# lyre_v1.net
KiCad netlist of a schematic drawn in EAGLE
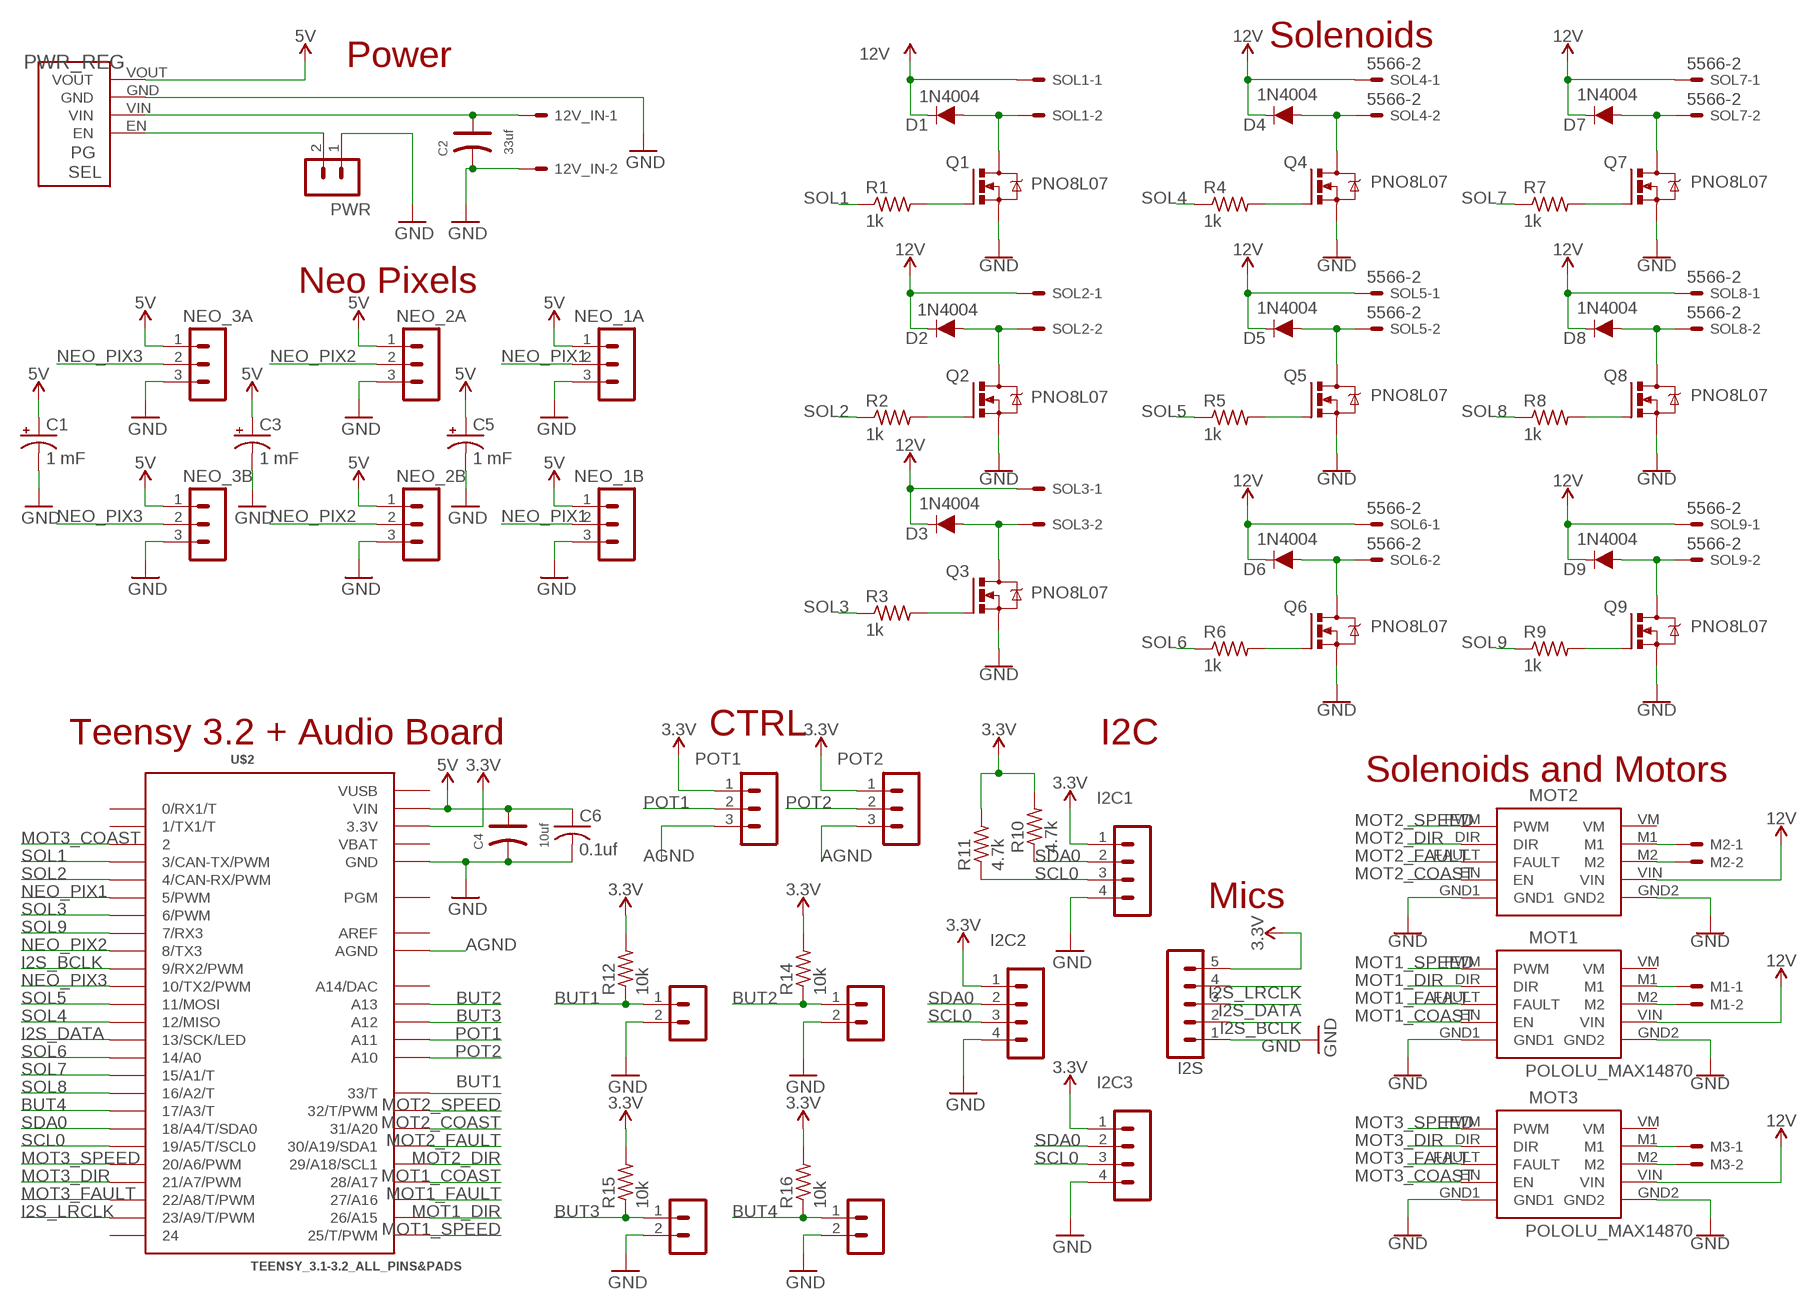
[diagram p0: schematic, sheet 1]

(export (version "E")
  (design (tool "Eeschema 10.0.6"))
  (components
    (comp (ref "12V_IN")
      (value "5566-2")
      (footprint "eagle-import:5566-2")
      (fields (field (name "MF") "MOLEX"))
      (libsource (lib "eagle-import") (part "5566-2"))
    )
    (comp (ref "BUT1")
      (value "B2B-PH-K")
      (footprint "eagle-import:B2B-PH-K")
      (libsource (lib "eagle-import") (part "B2B-PH-K"))
    )
    (comp (ref "BUT2")
      (value "B2B-PH-K")
      (footprint "eagle-import:B2B-PH-K")
      (libsource (lib "eagle-import") (part "B2B-PH-K"))
    )
    (comp (ref "BUT3")
      (value "B2B-PH-K")
      (footprint "eagle-import:B2B-PH-K")
      (libsource (lib "eagle-import") (part "B2B-PH-K"))
    )
    (comp (ref "BUT4")
      (value "B2B-PH-K")
      (footprint "eagle-import:B2B-PH-K")
      (libsource (lib "eagle-import") (part "B2B-PH-K"))
    )
    (comp (ref "C1")
      (value "1 mF")
      (footprint "eagle-import:UD-10X10_NICHICON")
      (libsource (lib "eagle-import") (part "CPOL-USUD-10X10"))
    )
    (comp (ref "C2")
      (value "33uf")
      (footprint "eagle-import:PC-D5.3MM")
      (fields (field (name "MPN") "KS 100uF/16V"))
      (libsource (lib "eagle-import") (part "DIP-ALUMINUM-47UF-16V(D5-H7MM)"))
    )
    (comp (ref "C3")
      (value "1 mF")
      (footprint "eagle-import:UD-10X10_NICHICON")
      (libsource (lib "eagle-import") (part "CPOL-USUD-10X10"))
    )
    (comp (ref "C4")
      (value "10uf")
      (footprint "eagle-import:PC-D5.3MM")
      (fields (field (name "MPN") "KS 100uF/16V"))
      (libsource (lib "eagle-import") (part "DIP-ALUMINUM-47UF-16V(D5-H7MM)"))
    )
    (comp (ref "C5")
      (value "1 mF")
      (footprint "eagle-import:UD-10X10_NICHICON")
      (libsource (lib "eagle-import") (part "CPOL-USUD-10X10"))
    )
    (comp (ref "C6")
      (value "0.1uf")
      (footprint "eagle-import:C2012")
      (libsource (lib "eagle-import") (part "C-USC2012"))
    )
    (comp (ref "D1")
      (value "1N4004")
      (footprint "eagle-import:DIOAD1138W86L465D235B")
      (libsource (lib "eagle-import") (part "1N4004"))
    )
    (comp (ref "D2")
      (value "1N4004")
      (footprint "eagle-import:DIOAD1138W86L465D235B")
      (libsource (lib "eagle-import") (part "1N4004"))
    )
    (comp (ref "D3")
      (value "1N4004")
      (footprint "eagle-import:DIOAD1138W86L465D235B")
      (libsource (lib "eagle-import") (part "1N4004"))
    )
    (comp (ref "D4")
      (value "1N4004")
      (footprint "eagle-import:DIOAD1138W86L465D235B")
      (libsource (lib "eagle-import") (part "1N4004"))
    )
    (comp (ref "D5")
      (value "1N4004")
      (footprint "eagle-import:DIOAD1138W86L465D235B")
      (libsource (lib "eagle-import") (part "1N4004"))
    )
    (comp (ref "D6")
      (value "1N4004")
      (footprint "eagle-import:DIOAD1138W86L465D235B")
      (libsource (lib "eagle-import") (part "1N4004"))
    )
    (comp (ref "D7")
      (value "1N4004")
      (footprint "eagle-import:DIOAD1138W86L465D235B")
      (libsource (lib "eagle-import") (part "1N4004"))
    )
    (comp (ref "D8")
      (value "1N4004")
      (footprint "eagle-import:DIOAD1138W86L465D235B")
      (libsource (lib "eagle-import") (part "1N4004"))
    )
    (comp (ref "D9")
      (value "1N4004")
      (footprint "eagle-import:DIOAD1138W86L465D235B")
      (libsource (lib "eagle-import") (part "1N4004"))
    )
    (comp (ref "I2C1")
      (value "B4B-PH-K")
      (footprint "eagle-import:B4B-PH-K")
      (libsource (lib "eagle-import") (part "B4B-PH-K"))
    )
    (comp (ref "I2C2")
      (value "B4B-PH-K")
      (footprint "eagle-import:B4B-PH-K")
      (libsource (lib "eagle-import") (part "B4B-PH-K"))
    )
    (comp (ref "I2C3")
      (value "B4B-PH-K")
      (footprint "eagle-import:B4B-PH-K")
      (libsource (lib "eagle-import") (part "B4B-PH-K"))
    )
    (comp (ref "I2S")
      (value "B5B-PH-K")
      (footprint "eagle-import:B5B-PH-K")
      (libsource (lib "eagle-import") (part "B5B-PH-K"))
    )
    (comp (ref "M1")
      (value "5566-2")
      (footprint "eagle-import:5566-2")
      (fields (field (name "MF") "MOLEX"))
      (libsource (lib "eagle-import") (part "5566-2"))
    )
    (comp (ref "M2")
      (value "5566-2")
      (footprint "eagle-import:5566-2")
      (fields (field (name "MF") "MOLEX"))
      (libsource (lib "eagle-import") (part "5566-2"))
    )
    (comp (ref "M3")
      (value "5566-2")
      (footprint "eagle-import:5566-2")
      (fields (field (name "MF") "MOLEX"))
      (libsource (lib "eagle-import") (part "5566-2"))
    )
    (comp (ref "MOT1")
      (value "POLOLU_MAX14870")
      (footprint "eagle-import:POLOLU_MAX14870")
      (libsource (lib "eagle-import") (part "POLOLU_MAX14870"))
    )
    (comp (ref "MOT2")
      (value "POLOLU_MAX14870")
      (footprint "eagle-import:POLOLU_MAX14870")
      (libsource (lib "eagle-import") (part "POLOLU_MAX14870"))
    )
    (comp (ref "MOT3")
      (value "POLOLU_MAX14870")
      (footprint "eagle-import:POLOLU_MAX14870")
      (libsource (lib "eagle-import") (part "POLOLU_MAX14870"))
    )
    (comp (ref "NEO_1A")
      (value "B3B-PH-K")
      (footprint "eagle-import:B3B-PH-K")
      (libsource (lib "eagle-import") (part "B3B-PH-K"))
    )
    (comp (ref "NEO_1B")
      (value "B3B-PH-K")
      (footprint "eagle-import:B3B-PH-K")
      (libsource (lib "eagle-import") (part "B3B-PH-K"))
    )
    (comp (ref "NEO_2A")
      (value "B3B-PH-K")
      (footprint "eagle-import:B3B-PH-K")
      (libsource (lib "eagle-import") (part "B3B-PH-K"))
    )
    (comp (ref "NEO_2B")
      (value "B3B-PH-K")
      (footprint "eagle-import:B3B-PH-K")
      (libsource (lib "eagle-import") (part "B3B-PH-K"))
    )
    (comp (ref "NEO_3A")
      (value "B3B-PH-K")
      (footprint "eagle-import:B3B-PH-K")
      (libsource (lib "eagle-import") (part "B3B-PH-K"))
    )
    (comp (ref "NEO_3B")
      (value "B3B-PH-K")
      (footprint "eagle-import:B3B-PH-K")
      (libsource (lib "eagle-import") (part "B3B-PH-K"))
    )
    (comp (ref "POT1")
      (value "B3B-PH-K")
      (footprint "eagle-import:B3B-PH-K")
      (libsource (lib "eagle-import") (part "B3B-PH-K"))
    )
    (comp (ref "POT2")
      (value "B3B-PH-K")
      (footprint "eagle-import:B3B-PH-K")
      (libsource (lib "eagle-import") (part "B3B-PH-K"))
    )
    (comp (ref "PWR")
      (value "B2B-PH-K")
      (footprint "eagle-import:B2B-PH-K")
      (libsource (lib "eagle-import") (part "B2B-PH-K"))
    )
    (comp (ref "PWR_REG")
      (value "S9V11F5S6CMA_MISSINIG_PINS")
      (footprint "eagle-import:S9V11F3S5CMA_MISSING_PINS")
      (libsource (lib "eagle-import") (part "S9V11F5S6CMA_MISSINIG_PINS"))
    )
    (comp (ref "Q1")
      (value "PNO8L07")
      (footprint "eagle-import:TO220BV")
      (libsource (lib "eagle-import") (part "IRF540"))
    )
    (comp (ref "Q2")
      (value "PNO8L07")
      (footprint "eagle-import:TO220BV")
      (libsource (lib "eagle-import") (part "IRF540"))
    )
    (comp (ref "Q3")
      (value "PNO8L07")
      (footprint "eagle-import:TO220BV")
      (libsource (lib "eagle-import") (part "IRF540"))
    )
    (comp (ref "Q4")
      (value "PNO8L07")
      (footprint "eagle-import:TO220BV")
      (libsource (lib "eagle-import") (part "IRF540"))
    )
    (comp (ref "Q5")
      (value "PNO8L07")
      (footprint "eagle-import:TO220BV")
      (libsource (lib "eagle-import") (part "IRF540"))
    )
    (comp (ref "Q6")
      (value "PNO8L07")
      (footprint "eagle-import:TO220BV")
      (libsource (lib "eagle-import") (part "IRF540"))
    )
    (comp (ref "Q7")
      (value "PNO8L07")
      (footprint "eagle-import:TO220BV")
      (libsource (lib "eagle-import") (part "IRF540"))
    )
    (comp (ref "Q8")
      (value "PNO8L07")
      (footprint "eagle-import:TO220BV")
      (libsource (lib "eagle-import") (part "IRF540"))
    )
    (comp (ref "Q9")
      (value "PNO8L07")
      (footprint "eagle-import:TO220BV")
      (libsource (lib "eagle-import") (part "IRF540"))
    )
    (comp (ref "R1")
      (value "1k")
      (footprint "eagle-import:R0805")
      (libsource (lib "eagle-import") (part "R-US_R0805"))
    )
    (comp (ref "R2")
      (value "1k")
      (footprint "eagle-import:R0805")
      (libsource (lib "eagle-import") (part "R-US_R0805"))
    )
    (comp (ref "R3")
      (value "1k")
      (footprint "eagle-import:R0805")
      (libsource (lib "eagle-import") (part "R-US_R0805"))
    )
    (comp (ref "R4")
      (value "1k")
      (footprint "eagle-import:R0805")
      (libsource (lib "eagle-import") (part "R-US_R0805"))
    )
    (comp (ref "R5")
      (value "1k")
      (footprint "eagle-import:R0805")
      (libsource (lib "eagle-import") (part "R-US_R0805"))
    )
    (comp (ref "R6")
      (value "1k")
      (footprint "eagle-import:R0805")
      (libsource (lib "eagle-import") (part "R-US_R0805"))
    )
    (comp (ref "R7")
      (value "1k")
      (footprint "eagle-import:R0805")
      (libsource (lib "eagle-import") (part "R-US_R0805"))
    )
    (comp (ref "R8")
      (value "1k")
      (footprint "eagle-import:R0805")
      (libsource (lib "eagle-import") (part "R-US_R0805"))
    )
    (comp (ref "R9")
      (value "1k")
      (footprint "eagle-import:R0805")
      (libsource (lib "eagle-import") (part "R-US_R0805"))
    )
    (comp (ref "R10")
      (value "4.7k")
      (footprint "eagle-import:R0805")
      (libsource (lib "eagle-import") (part "R-US_R0805"))
    )
    (comp (ref "R11")
      (value "4.7k")
      (footprint "eagle-import:R0805")
      (libsource (lib "eagle-import") (part "R-US_R0805"))
    )
    (comp (ref "R12")
      (value "10k")
      (footprint "eagle-import:R0805")
      (libsource (lib "eagle-import") (part "R-US_R0805"))
    )
    (comp (ref "R14")
      (value "10k")
      (footprint "eagle-import:R0805")
      (libsource (lib "eagle-import") (part "R-US_R0805"))
    )
    (comp (ref "R15")
      (value "10k")
      (footprint "eagle-import:R0805")
      (libsource (lib "eagle-import") (part "R-US_R0805"))
    )
    (comp (ref "R16")
      (value "10k")
      (footprint "eagle-import:R0805")
      (libsource (lib "eagle-import") (part "R-US_R0805"))
    )
    (comp (ref "SOL1")
      (value "5566-2")
      (footprint "eagle-import:5566-2")
      (fields (field (name "MF") "MOLEX"))
      (libsource (lib "eagle-import") (part "5566-2"))
    )
    (comp (ref "SOL2")
      (value "5566-2")
      (footprint "eagle-import:5566-2")
      (fields (field (name "MF") "MOLEX"))
      (libsource (lib "eagle-import") (part "5566-2"))
    )
    (comp (ref "SOL3")
      (value "5566-2")
      (footprint "eagle-import:5566-2")
      (fields (field (name "MF") "MOLEX"))
      (libsource (lib "eagle-import") (part "5566-2"))
    )
    (comp (ref "SOL4")
      (value "5566-2")
      (footprint "eagle-import:5566-2")
      (fields (field (name "MF") "MOLEX"))
      (libsource (lib "eagle-import") (part "5566-2"))
    )
    (comp (ref "SOL5")
      (value "5566-2")
      (footprint "eagle-import:5566-2")
      (fields (field (name "MF") "MOLEX"))
      (libsource (lib "eagle-import") (part "5566-2"))
    )
    (comp (ref "SOL6")
      (value "5566-2")
      (footprint "eagle-import:5566-2")
      (fields (field (name "MF") "MOLEX"))
      (libsource (lib "eagle-import") (part "5566-2"))
    )
    (comp (ref "SOL7")
      (value "5566-2")
      (footprint "eagle-import:5566-2")
      (fields (field (name "MF") "MOLEX"))
      (libsource (lib "eagle-import") (part "5566-2"))
    )
    (comp (ref "SOL8")
      (value "5566-2")
      (footprint "eagle-import:5566-2")
      (fields (field (name "MF") "MOLEX"))
      (libsource (lib "eagle-import") (part "5566-2"))
    )
    (comp (ref "SOL9")
      (value "5566-2")
      (footprint "eagle-import:5566-2")
      (fields (field (name "MF") "MOLEX"))
      (libsource (lib "eagle-import") (part "5566-2"))
    )
    (comp (ref "U$2")
      (value "TEENSY_3.1-3.2_ALL_PINS&PADS")
      (footprint "eagle-import:TEENSY_3.0-3.2_ALL_PINS_&_PADS")
      (libsource (lib "eagle-import") (part "TEENSY_3.1-3.2_ALL_PINS&PADS"))
    )
  )
  (nets
    (net (code "1") (name "/AGND") (class "Default")
      (node (ref "POT1") (pin "3") (pinfunction "3_3") (pintype "passive"))
      (node (ref "POT2") (pin "3") (pinfunction "3_3") (pintype "passive"))
      (node (ref "U$2") (pin "AGND") (pinfunction "AGND_AGND") (pintype "power_in"))
    )
    (net (code "2") (name "/AREF") (class "Default")
      (node (ref "U$2") (pin "AREF") (pinfunction "AREF_AREF") (pintype "power_in"))
    )
    (net (code "3") (name "/BUT1") (class "Default")
      (node (ref "BUT1") (pin "1") (pinfunction "1_1") (pintype "passive"))
      (node (ref "R12") (pin "1") (pinfunction "1_1") (pintype "passive"))
      (node (ref "U$2") (pin "33") (pinfunction "33/T_33") (pintype "bidirectional"))
    )
    (net (code "4") (name "/BUT2") (class "Default")
      (node (ref "BUT2") (pin "1") (pinfunction "1_1") (pintype "passive"))
      (node (ref "R14") (pin "1") (pinfunction "1_1") (pintype "passive"))
      (node (ref "U$2") (pin "A13") (pinfunction "A13_A13") (pintype "bidirectional"))
    )
    (net (code "5") (name "/BUT3") (class "Default")
      (node (ref "BUT3") (pin "1") (pinfunction "1_1") (pintype "passive"))
      (node (ref "R15") (pin "1") (pinfunction "1_1") (pintype "passive"))
      (node (ref "U$2") (pin "A12") (pinfunction "A12_A12") (pintype "bidirectional"))
    )
    (net (code "6") (name "/BUT4") (class "Default")
      (node (ref "BUT4") (pin "1") (pinfunction "1_1") (pintype "passive"))
      (node (ref "R16") (pin "1") (pinfunction "1_1") (pintype "passive"))
      (node (ref "U$2") (pin "17/A3") (pinfunction "17/A3/T_17/A3") (pintype "bidirectional"))
    )
    (net (code "7") (name "/I2S_BCLK") (class "Default")
      (node (ref "I2S") (pin "2") (pinfunction "2_2") (pintype "passive"))
      (node (ref "U$2") (pin "9") (pinfunction "9/RX2/PWM_9") (pintype "bidirectional"))
    )
    (net (code "8") (name "/I2S_DATA") (class "Default")
      (node (ref "I2S") (pin "3") (pinfunction "3_3") (pintype "passive"))
      (node (ref "U$2") (pin "13") (pinfunction "13/SCK/LED_13") (pintype "bidirectional"))
    )
    (net (code "9") (name "/I2S_LRCLK") (class "Default")
      (node (ref "I2S") (pin "4") (pinfunction "4_4") (pintype "passive"))
      (node (ref "U$2") (pin "23/A9") (pinfunction "23/A9/T/PWM_23/A9") (pintype "bidirectional"))
    )
    (net (code "10") (name "/MOT1_COAST") (class "Default")
      (node (ref "MOT1") (pin "EN") (pinfunction "EN_EN") (pintype "bidirectional"))
      (node (ref "U$2") (pin "28") (pinfunction "28/A17_28") (pintype "bidirectional"))
    )
    (net (code "11") (name "/MOT1_DIR") (class "Default")
      (node (ref "MOT1") (pin "DIR") (pinfunction "DIR_DIR") (pintype "bidirectional"))
      (node (ref "U$2") (pin "26") (pinfunction "26/A15_26") (pintype "bidirectional"))
    )
    (net (code "12") (name "/MOT1_FAULT") (class "Default")
      (node (ref "MOT1") (pin "FAULT") (pinfunction "FAULT_FAULT") (pintype "bidirectional"))
      (node (ref "U$2") (pin "27") (pinfunction "27/A16_27") (pintype "bidirectional"))
    )
    (net (code "13") (name "/MOT1_SPEED") (class "Default")
      (node (ref "MOT1") (pin "PWM") (pinfunction "PWM_PWM") (pintype "bidirectional"))
      (node (ref "U$2") (pin "25") (pinfunction "25/T/PWM_25") (pintype "bidirectional"))
    )
    (net (code "14") (name "/MOT2_COAST") (class "Default")
      (node (ref "MOT2") (pin "EN") (pinfunction "EN_EN") (pintype "bidirectional"))
      (node (ref "U$2") (pin "31") (pinfunction "31/A20_31") (pintype "bidirectional"))
    )
    (net (code "15") (name "/MOT2_DIR") (class "Default")
      (node (ref "MOT2") (pin "DIR") (pinfunction "DIR_DIR") (pintype "bidirectional"))
      (node (ref "U$2") (pin "29") (pinfunction "29/A18/SCL1_29") (pintype "bidirectional"))
    )
    (net (code "16") (name "/MOT2_FAULT") (class "Default")
      (node (ref "MOT2") (pin "FAULT") (pinfunction "FAULT_FAULT") (pintype "bidirectional"))
      (node (ref "U$2") (pin "30") (pinfunction "30/A19/SDA1_30") (pintype "bidirectional"))
    )
    (net (code "17") (name "/MOT2_SPEED") (class "Default")
      (node (ref "MOT2") (pin "PWM") (pinfunction "PWM_PWM") (pintype "bidirectional"))
      (node (ref "U$2") (pin "32") (pinfunction "32/T/PWM_32") (pintype "bidirectional"))
    )
    (net (code "18") (name "/MOT3_COAST") (class "Default")
      (node (ref "MOT3") (pin "EN") (pinfunction "EN_EN") (pintype "bidirectional"))
      (node (ref "U$2") (pin "2") (pinfunction "2_2") (pintype "bidirectional"))
    )
    (net (code "19") (name "/MOT3_DIR") (class "Default")
      (node (ref "MOT3") (pin "DIR") (pinfunction "DIR_DIR") (pintype "bidirectional"))
      (node (ref "U$2") (pin "21/A7") (pinfunction "21/A7/PWM_21/A7") (pintype "bidirectional"))
    )
    (net (code "20") (name "/MOT3_FAULT") (class "Default")
      (node (ref "MOT3") (pin "FAULT") (pinfunction "FAULT_FAULT") (pintype "bidirectional"))
      (node (ref "U$2") (pin "22/A8") (pinfunction "22/A8/T/PWM_22/A8") (pintype "bidirectional"))
    )
    (net (code "21") (name "/MOT3_SPEED") (class "Default")
      (node (ref "MOT3") (pin "PWM") (pinfunction "PWM_PWM") (pintype "bidirectional"))
      (node (ref "U$2") (pin "20/A6") (pinfunction "20/A6/PWM_20/A6") (pintype "bidirectional"))
    )
    (net (code "22") (name "/NEO_PIX1") (class "Default")
      (node (ref "NEO_1A") (pin "2") (pinfunction "2_2") (pintype "passive"))
      (node (ref "NEO_1B") (pin "2") (pinfunction "2_2") (pintype "passive"))
      (node (ref "U$2") (pin "5") (pinfunction "5/PWM_5") (pintype "bidirectional"))
    )
    (net (code "23") (name "/NEO_PIX2") (class "Default")
      (node (ref "NEO_2A") (pin "2") (pinfunction "2_2") (pintype "passive"))
      (node (ref "NEO_2B") (pin "2") (pinfunction "2_2") (pintype "passive"))
      (node (ref "U$2") (pin "8") (pinfunction "8/TX3_8") (pintype "bidirectional"))
    )
    (net (code "24") (name "/NEO_PIX3") (class "Default")
      (node (ref "NEO_3A") (pin "2") (pinfunction "2_2") (pintype "passive"))
      (node (ref "NEO_3B") (pin "2") (pinfunction "2_2") (pintype "passive"))
      (node (ref "U$2") (pin "10") (pinfunction "10/TX2/PWM_10") (pintype "bidirectional"))
    )
    (net (code "25") (name "/POT1") (class "Default")
      (node (ref "POT1") (pin "2") (pinfunction "2_2") (pintype "passive"))
      (node (ref "U$2") (pin "A11") (pinfunction "A11_A11") (pintype "bidirectional"))
    )
    (net (code "26") (name "/POT2") (class "Default")
      (node (ref "POT2") (pin "2") (pinfunction "2_2") (pintype "passive"))
      (node (ref "U$2") (pin "A10") (pinfunction "A10_A10") (pintype "bidirectional"))
    )
    (net (code "27") (name "/SCL0") (class "Default")
      (node (ref "I2C1") (pin "3") (pinfunction "3_3") (pintype "passive"))
      (node (ref "I2C2") (pin "3") (pinfunction "3_3") (pintype "passive"))
      (node (ref "I2C3") (pin "3") (pinfunction "3_3") (pintype "passive"))
      (node (ref "R11") (pin "1") (pinfunction "1_1") (pintype "passive"))
      (node (ref "U$2") (pin "19/A5") (pinfunction "19/A5/T/SCL0_19/A5") (pintype "bidirectional"))
    )
    (net (code "28") (name "/SDA0") (class "Default")
      (node (ref "I2C1") (pin "2") (pinfunction "2_2") (pintype "passive"))
      (node (ref "I2C2") (pin "2") (pinfunction "2_2") (pintype "passive"))
      (node (ref "I2C3") (pin "2") (pinfunction "2_2") (pintype "passive"))
      (node (ref "R10") (pin "1") (pinfunction "1_1") (pintype "passive"))
      (node (ref "U$2") (pin "18/A4") (pinfunction "18/A4/T/SDA0_18/A4") (pintype "bidirectional"))
    )
    (net (code "29") (name "/SOL1") (class "Default")
      (node (ref "R1") (pin "1") (pinfunction "1_1") (pintype "passive"))
      (node (ref "U$2") (pin "3") (pinfunction "3/CAN-TX/PWM_3") (pintype "bidirectional"))
    )
    (net (code "30") (name "/SOL2") (class "Default")
      (node (ref "R2") (pin "1") (pinfunction "1_1") (pintype "passive"))
      (node (ref "U$2") (pin "4") (pinfunction "4/CAN-RX/PWM_4") (pintype "bidirectional"))
    )
    (net (code "31") (name "/SOL3") (class "Default")
      (node (ref "R3") (pin "1") (pinfunction "1_1") (pintype "passive"))
      (node (ref "U$2") (pin "6") (pinfunction "6/PWM_6") (pintype "bidirectional"))
    )
    (net (code "32") (name "/SOL4") (class "Default")
      (node (ref "R4") (pin "1") (pinfunction "1_1") (pintype "passive"))
      (node (ref "U$2") (pin "12") (pinfunction "12/MISO_12") (pintype "bidirectional"))
    )
    (net (code "33") (name "/SOL5") (class "Default")
      (node (ref "R5") (pin "1") (pinfunction "1_1") (pintype "passive"))
      (node (ref "U$2") (pin "11") (pinfunction "11/MOSI_11") (pintype "bidirectional"))
    )
    (net (code "34") (name "/SOL6") (class "Default")
      (node (ref "R6") (pin "1") (pinfunction "1_1") (pintype "passive"))
      (node (ref "U$2") (pin "14/A0") (pinfunction "14/A0_14/A0") (pintype "bidirectional"))
    )
    (net (code "35") (name "/SOL7") (class "Default")
      (node (ref "R7") (pin "1") (pinfunction "1_1") (pintype "passive"))
      (node (ref "U$2") (pin "15/A1") (pinfunction "15/A1/T_15/A1") (pintype "bidirectional"))
    )
    (net (code "36") (name "/SOL8") (class "Default")
      (node (ref "R8") (pin "1") (pinfunction "1_1") (pintype "passive"))
      (node (ref "U$2") (pin "16/A2") (pinfunction "16/A2/T_16/A2") (pintype "bidirectional"))
    )
    (net (code "37") (name "/SOL9") (class "Default")
      (node (ref "R9") (pin "1") (pinfunction "1_1") (pintype "passive"))
      (node (ref "U$2") (pin "7") (pinfunction "7/RX3_7") (pintype "bidirectional"))
    )
    (net (code "38") (name "/VBAT") (class "Default")
      (node (ref "U$2") (pin "VBAT") (pinfunction "VBAT_VBAT") (pintype "power_in"))
    )
    (net (code "39") (name "/VUSB") (class "Default")
      (node (ref "U$2") (pin "VUSB") (pinfunction "VUSB_VUSB") (pintype "power_in"))
    )
    (net (code "40") (name "3.3V") (class "Default")
      (node (ref "I2C1") (pin "1") (pinfunction "1_1") (pintype "passive"))
      (node (ref "I2C2") (pin "1") (pinfunction "1_1") (pintype "passive"))
      (node (ref "I2C3") (pin "1") (pinfunction "1_1") (pintype "passive"))
      (node (ref "I2S") (pin "5") (pinfunction "5_5") (pintype "passive"))
      (node (ref "POT1") (pin "1") (pinfunction "1_1") (pintype "passive"))
      (node (ref "POT2") (pin "1") (pinfunction "1_1") (pintype "passive"))
      (node (ref "R10") (pin "2") (pinfunction "2_2") (pintype "passive"))
      (node (ref "R11") (pin "2") (pinfunction "2_2") (pintype "passive"))
      (node (ref "R12") (pin "2") (pinfunction "2_2") (pintype "passive"))
      (node (ref "R14") (pin "2") (pinfunction "2_2") (pintype "passive"))
      (node (ref "R15") (pin "2") (pinfunction "2_2") (pintype "passive"))
      (node (ref "R16") (pin "2") (pinfunction "2_2") (pintype "passive"))
      (node (ref "U$2") (pin "3.3V") (pinfunction "3.3V_3.3V") (pintype "power_in"))
      (node (ref "U$2") (pin "3.3V1") (pinfunction "3.3V_3.3V1") (pintype "power_in"))
      (node (ref "U$2") (pin "3.3V2") (pinfunction "3.3V_3.3V2") (pintype "power_in"))
    )
    (net (code "41") (name "5V") (class "Default")
      (node (ref "C1") (pin "+") (pinfunction "+_+") (pintype "passive"))
      (node (ref "C3") (pin "+") (pinfunction "+_+") (pintype "passive"))
      (node (ref "C4") (pin "+") (pinfunction "+_+") (pintype "passive"))
      (node (ref "C5") (pin "+") (pinfunction "+_+") (pintype "passive"))
      (node (ref "C6") (pin "1") (pinfunction "1_1") (pintype "passive"))
      (node (ref "NEO_1A") (pin "1") (pinfunction "1_1") (pintype "passive"))
      (node (ref "NEO_1B") (pin "1") (pinfunction "1_1") (pintype "passive"))
      (node (ref "NEO_2A") (pin "1") (pinfunction "1_1") (pintype "passive"))
      (node (ref "NEO_2B") (pin "1") (pinfunction "1_1") (pintype "passive"))
      (node (ref "NEO_3A") (pin "1") (pinfunction "1_1") (pintype "passive"))
      (node (ref "NEO_3B") (pin "1") (pinfunction "1_1") (pintype "passive"))
      (node (ref "PWR_REG") (pin "VOUT") (pinfunction "VOUT_VOUT") (pintype "bidirectional"))
      (node (ref "U$2") (pin "VIN") (pinfunction "VIN_VIN") (pintype "power_in"))
    )
    (net (code "42") (name "12V") (class "Default")
      (node (ref "12V_IN") (pin "1") (pinfunction "S_1") (pintype "passive"))
      (node (ref "C2") (pin "+") (pinfunction "+_+") (pintype "passive"))
      (node (ref "D1") (pin "2") (pinfunction "C_2") (pintype "passive"))
      (node (ref "D2") (pin "2") (pinfunction "C_2") (pintype "passive"))
      (node (ref "D3") (pin "2") (pinfunction "C_2") (pintype "passive"))
      (node (ref "D4") (pin "2") (pinfunction "C_2") (pintype "passive"))
      (node (ref "D5") (pin "2") (pinfunction "C_2") (pintype "passive"))
      (node (ref "D6") (pin "2") (pinfunction "C_2") (pintype "passive"))
      (node (ref "D7") (pin "2") (pinfunction "C_2") (pintype "passive"))
      (node (ref "D8") (pin "2") (pinfunction "C_2") (pintype "passive"))
      (node (ref "D9") (pin "2") (pinfunction "C_2") (pintype "passive"))
      (node (ref "MOT1") (pin "VIN") (pinfunction "VIN_VIN") (pintype "bidirectional"))
      (node (ref "MOT2") (pin "VIN") (pinfunction "VIN_VIN") (pintype "bidirectional"))
      (node (ref "MOT3") (pin "VIN") (pinfunction "VIN_VIN") (pintype "bidirectional"))
      (node (ref "PWR_REG") (pin "VIN") (pinfunction "VIN_VIN") (pintype "bidirectional"))
      (node (ref "SOL1") (pin "1") (pinfunction "S_1") (pintype "passive"))
      (node (ref "SOL2") (pin "1") (pinfunction "S_1") (pintype "passive"))
      (node (ref "SOL3") (pin "1") (pinfunction "S_1") (pintype "passive"))
      (node (ref "SOL4") (pin "1") (pinfunction "S_1") (pintype "passive"))
      (node (ref "SOL5") (pin "1") (pinfunction "S_1") (pintype "passive"))
      (node (ref "SOL6") (pin "1") (pinfunction "S_1") (pintype "passive"))
      (node (ref "SOL7") (pin "1") (pinfunction "S_1") (pintype "passive"))
      (node (ref "SOL8") (pin "1") (pinfunction "S_1") (pintype "passive"))
      (node (ref "SOL9") (pin "1") (pinfunction "S_1") (pintype "passive"))
    )
    (net (code "43") (name "GND") (class "Default")
      (node (ref "12V_IN") (pin "2") (pinfunction "S_2") (pintype "passive"))
      (node (ref "BUT1") (pin "2") (pinfunction "2_2") (pintype "passive"))
      (node (ref "BUT2") (pin "2") (pinfunction "2_2") (pintype "passive"))
      (node (ref "BUT3") (pin "2") (pinfunction "2_2") (pintype "passive"))
      (node (ref "BUT4") (pin "2") (pinfunction "2_2") (pintype "passive"))
      (node (ref "C1") (pin "-") (pinfunction "-_-") (pintype "passive"))
      (node (ref "C2") (pin "-") (pinfunction "-_-") (pintype "passive"))
      (node (ref "C3") (pin "-") (pinfunction "-_-") (pintype "passive"))
      (node (ref "C4") (pin "-") (pinfunction "-_-") (pintype "passive"))
      (node (ref "C5") (pin "-") (pinfunction "-_-") (pintype "passive"))
      (node (ref "C6") (pin "2") (pinfunction "2_2") (pintype "passive"))
      (node (ref "I2C1") (pin "4") (pinfunction "4_4") (pintype "passive"))
      (node (ref "I2C2") (pin "4") (pinfunction "4_4") (pintype "passive"))
      (node (ref "I2C3") (pin "4") (pinfunction "4_4") (pintype "passive"))
      (node (ref "I2S") (pin "1") (pinfunction "1_1") (pintype "passive"))
      (node (ref "MOT1") (pin "GND1") (pinfunction "GND1_GND1") (pintype "bidirectional"))
      (node (ref "MOT1") (pin "GND2") (pinfunction "GND2_GND2") (pintype "bidirectional"))
      (node (ref "MOT2") (pin "GND1") (pinfunction "GND1_GND1") (pintype "bidirectional"))
      (node (ref "MOT2") (pin "GND2") (pinfunction "GND2_GND2") (pintype "bidirectional"))
      (node (ref "MOT3") (pin "GND1") (pinfunction "GND1_GND1") (pintype "bidirectional"))
      (node (ref "MOT3") (pin "GND2") (pinfunction "GND2_GND2") (pintype "bidirectional"))
      (node (ref "NEO_1A") (pin "3") (pinfunction "3_3") (pintype "passive"))
      (node (ref "NEO_1B") (pin "3") (pinfunction "3_3") (pintype "passive"))
      (node (ref "NEO_2A") (pin "3") (pinfunction "3_3") (pintype "passive"))
      (node (ref "NEO_2B") (pin "3") (pinfunction "3_3") (pintype "passive"))
      (node (ref "NEO_3A") (pin "3") (pinfunction "3_3") (pintype "passive"))
      (node (ref "NEO_3B") (pin "3") (pinfunction "3_3") (pintype "passive"))
      (node (ref "PWR") (pin "1") (pinfunction "1_1") (pintype "passive"))
      (node (ref "PWR_REG") (pin "GND") (pinfunction "GND_GND") (pintype "bidirectional"))
      (node (ref "Q1") (pin "S") (pinfunction "S_S") (pintype "passive"))
      (node (ref "Q2") (pin "S") (pinfunction "S_S") (pintype "passive"))
      (node (ref "Q3") (pin "S") (pinfunction "S_S") (pintype "passive"))
      (node (ref "Q4") (pin "S") (pinfunction "S_S") (pintype "passive"))
      (node (ref "Q5") (pin "S") (pinfunction "S_S") (pintype "passive"))
      (node (ref "Q6") (pin "S") (pinfunction "S_S") (pintype "passive"))
      (node (ref "Q7") (pin "S") (pinfunction "S_S") (pintype "passive"))
      (node (ref "Q8") (pin "S") (pinfunction "S_S") (pintype "passive"))
      (node (ref "Q9") (pin "S") (pinfunction "S_S") (pintype "passive"))
      (node (ref "U$2") (pin "GND") (pinfunction "GND_GND") (pintype "power_in"))
      (node (ref "U$2") (pin "GND1") (pinfunction "GND_GND1") (pintype "power_in"))
      (node (ref "U$2") (pin "GND2") (pinfunction "GND_GND2") (pintype "power_in"))
    )
    (net (code "44") (name "Net-(D1-A)") (class "Default")
      (node (ref "D1") (pin "1") (pinfunction "A_1") (pintype "passive"))
      (node (ref "Q1") (pin "D") (pinfunction "D_D") (pintype "passive"))
      (node (ref "SOL1") (pin "2") (pinfunction "S_2") (pintype "passive"))
    )
    (net (code "45") (name "Net-(D2-A)") (class "Default")
      (node (ref "D2") (pin "1") (pinfunction "A_1") (pintype "passive"))
      (node (ref "Q2") (pin "D") (pinfunction "D_D") (pintype "passive"))
      (node (ref "SOL2") (pin "2") (pinfunction "S_2") (pintype "passive"))
    )
    (net (code "46") (name "Net-(D3-A)") (class "Default")
      (node (ref "D3") (pin "1") (pinfunction "A_1") (pintype "passive"))
      (node (ref "Q3") (pin "D") (pinfunction "D_D") (pintype "passive"))
      (node (ref "SOL3") (pin "2") (pinfunction "S_2") (pintype "passive"))
    )
    (net (code "47") (name "Net-(D4-A)") (class "Default")
      (node (ref "D4") (pin "1") (pinfunction "A_1") (pintype "passive"))
      (node (ref "Q4") (pin "D") (pinfunction "D_D") (pintype "passive"))
      (node (ref "SOL4") (pin "2") (pinfunction "S_2") (pintype "passive"))
    )
    (net (code "48") (name "Net-(D5-A)") (class "Default")
      (node (ref "D5") (pin "1") (pinfunction "A_1") (pintype "passive"))
      (node (ref "Q5") (pin "D") (pinfunction "D_D") (pintype "passive"))
      (node (ref "SOL5") (pin "2") (pinfunction "S_2") (pintype "passive"))
    )
    (net (code "49") (name "Net-(D6-A)") (class "Default")
      (node (ref "D6") (pin "1") (pinfunction "A_1") (pintype "passive"))
      (node (ref "Q6") (pin "D") (pinfunction "D_D") (pintype "passive"))
      (node (ref "SOL6") (pin "2") (pinfunction "S_2") (pintype "passive"))
    )
    (net (code "50") (name "Net-(D7-A)") (class "Default")
      (node (ref "D7") (pin "1") (pinfunction "A_1") (pintype "passive"))
      (node (ref "Q7") (pin "D") (pinfunction "D_D") (pintype "passive"))
      (node (ref "SOL7") (pin "2") (pinfunction "S_2") (pintype "passive"))
    )
    (net (code "51") (name "Net-(D8-A)") (class "Default")
      (node (ref "D8") (pin "1") (pinfunction "A_1") (pintype "passive"))
      (node (ref "Q8") (pin "D") (pinfunction "D_D") (pintype "passive"))
      (node (ref "SOL8") (pin "2") (pinfunction "S_2") (pintype "passive"))
    )
    (net (code "52") (name "Net-(D9-A)") (class "Default")
      (node (ref "D9") (pin "1") (pinfunction "A_1") (pintype "passive"))
      (node (ref "Q9") (pin "D") (pinfunction "D_D") (pintype "passive"))
      (node (ref "SOL9") (pin "2") (pinfunction "S_2") (pintype "passive"))
    )
    (net (code "53") (name "Net-(M1A-S)") (class "Default")
      (node (ref "M1") (pin "1") (pinfunction "S_1") (pintype "passive"))
      (node (ref "MOT1") (pin "M1") (pinfunction "M1_M1") (pintype "bidirectional"))
    )
    (net (code "54") (name "Net-(M1B-S)") (class "Default")
      (node (ref "M1") (pin "2") (pinfunction "S_2") (pintype "passive"))
      (node (ref "MOT1") (pin "M2") (pinfunction "M2_M2") (pintype "bidirectional"))
    )
    (net (code "55") (name "Net-(M2A-S)") (class "Default")
      (node (ref "M2") (pin "1") (pinfunction "S_1") (pintype "passive"))
      (node (ref "MOT2") (pin "M1") (pinfunction "M1_M1") (pintype "bidirectional"))
    )
    (net (code "56") (name "Net-(M2B-S)") (class "Default")
      (node (ref "M2") (pin "2") (pinfunction "S_2") (pintype "passive"))
      (node (ref "MOT2") (pin "M2") (pinfunction "M2_M2") (pintype "bidirectional"))
    )
    (net (code "57") (name "Net-(M3A-S)") (class "Default")
      (node (ref "M3") (pin "1") (pinfunction "S_1") (pintype "passive"))
      (node (ref "MOT3") (pin "M1") (pinfunction "M1_M1") (pintype "bidirectional"))
    )
    (net (code "58") (name "Net-(M3B-S)") (class "Default")
      (node (ref "M3") (pin "2") (pinfunction "S_2") (pintype "passive"))
      (node (ref "MOT3") (pin "M2") (pinfunction "M2_M2") (pintype "bidirectional"))
    )
    (net (code "59") (name "Net-(PWR-Pad2)") (class "Default")
      (node (ref "PWR") (pin "2") (pinfunction "2_2") (pintype "passive"))
      (node (ref "PWR_REG") (pin "EN") (pinfunction "EN_EN") (pintype "bidirectional"))
    )
    (net (code "60") (name "Net-(Q1-PadG)") (class "Default")
      (node (ref "Q1") (pin "G") (pinfunction "G_G") (pintype "passive"))
      (node (ref "R1") (pin "2") (pinfunction "2_2") (pintype "passive"))
    )
    (net (code "61") (name "Net-(Q2-PadG)") (class "Default")
      (node (ref "Q2") (pin "G") (pinfunction "G_G") (pintype "passive"))
      (node (ref "R2") (pin "2") (pinfunction "2_2") (pintype "passive"))
    )
    (net (code "62") (name "Net-(Q3-PadG)") (class "Default")
      (node (ref "Q3") (pin "G") (pinfunction "G_G") (pintype "passive"))
      (node (ref "R3") (pin "2") (pinfunction "2_2") (pintype "passive"))
    )
    (net (code "63") (name "Net-(Q4-PadG)") (class "Default")
      (node (ref "Q4") (pin "G") (pinfunction "G_G") (pintype "passive"))
      (node (ref "R4") (pin "2") (pinfunction "2_2") (pintype "passive"))
    )
    (net (code "64") (name "Net-(Q5-PadG)") (class "Default")
      (node (ref "Q5") (pin "G") (pinfunction "G_G") (pintype "passive"))
      (node (ref "R5") (pin "2") (pinfunction "2_2") (pintype "passive"))
    )
    (net (code "65") (name "Net-(Q6-PadG)") (class "Default")
      (node (ref "Q6") (pin "G") (pinfunction "G_G") (pintype "passive"))
      (node (ref "R6") (pin "2") (pinfunction "2_2") (pintype "passive"))
    )
    (net (code "66") (name "Net-(Q7-PadG)") (class "Default")
      (node (ref "Q7") (pin "G") (pinfunction "G_G") (pintype "passive"))
      (node (ref "R7") (pin "2") (pinfunction "2_2") (pintype "passive"))
    )
    (net (code "67") (name "Net-(Q8-PadG)") (class "Default")
      (node (ref "Q8") (pin "G") (pinfunction "G_G") (pintype "passive"))
      (node (ref "R8") (pin "2") (pinfunction "2_2") (pintype "passive"))
    )
    (net (code "68") (name "Net-(Q9-PadG)") (class "Default")
      (node (ref "Q9") (pin "G") (pinfunction "G_G") (pintype "passive"))
      (node (ref "R9") (pin "2") (pinfunction "2_2") (pintype "passive"))
    )
    (net (code "69") (name "unconnected-(MOT1-PadVM)") (class "Default")
      (node (ref "MOT1") (pin "VM") (pinfunction "VM_VM") (pintype "bidirectional"))
    )
    (net (code "70") (name "unconnected-(MOT2-PadVM)") (class "Default")
      (node (ref "MOT2") (pin "VM") (pinfunction "VM_VM") (pintype "bidirectional"))
    )
    (net (code "71") (name "unconnected-(MOT3-PadVM)") (class "Default")
      (node (ref "MOT3") (pin "VM") (pinfunction "VM_VM") (pintype "bidirectional"))
    )
    (net (code "72") (name "unconnected-(U$2-0{slash}RX1{slash}T-Pad0)") (class "Default")
      (node (ref "U$2") (pin "0") (pinfunction "0/RX1/T_0") (pintype "bidirectional"))
    )
    (net (code "73") (name "unconnected-(U$2-1{slash}TX1{slash}T-Pad1)") (class "Default")
      (node (ref "U$2") (pin "1") (pinfunction "1/TX1/T_1") (pintype "bidirectional"))
    )
    (net (code "74") (name "unconnected-(U$2-A14{slash}DAC-PadRESET{slash}DAC)") (class "Default")
      (node (ref "U$2") (pin "RESET/DAC") (pinfunction "A14/DAC_RESET/DAC") (pintype "bidirectional"))
    )
    (net (code "75") (name "unconnected-(U$2-Pad24)") (class "Default")
      (node (ref "U$2") (pin "24") (pinfunction "24_24") (pintype "bidirectional"))
    )
    (net (code "76") (name "unconnected-(U$2-PadPGM)") (class "Default")
      (node (ref "U$2") (pin "PGM") (pinfunction "PGM_PGM") (pintype "bidirectional"))
    )
  )
)
